# lm2576-adj_powersupply.net
KiCad netlist of a schematic drawn in EAGLE
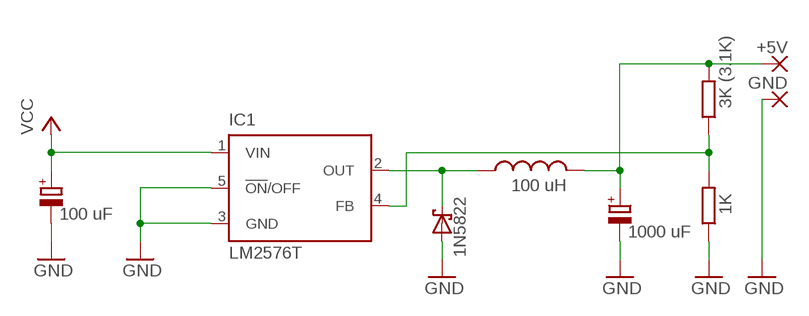
[diagram p0: schematic, sheet 1]

(export (version "E")
  (design (tool "Eeschema 10.0.6"))
  (components
    (comp (ref "+5V")
      (value "2,15/1,0")
      (footprint "eagle-import:2,15_1,0")
      (libsource (lib "eagle-import") (part "2,15/1,0"))
    )
    (comp (ref "C1")
      (value "100 uF")
      (footprint "eagle-import:E7,5-16")
      (libsource (lib "eagle-import") (part "CPOL-EUE7.5-16"))
    )
    (comp (ref "C2")
      (value "1000 uF")
      (footprint "eagle-import:E7,5-16")
      (libsource (lib "eagle-import") (part "CPOL-EUE7.5-16"))
    )
    (comp (ref "D1")
      (value "1N5822")
      (footprint "eagle-import:C4111-15")
      (libsource (lib "eagle-import") (part "1N5908"))
    )
    (comp (ref "GND")
      (value "GND")
      (footprint "eagle-import:2,15_1,0")
      (libsource (lib "eagle-import") (part "2,15/1,0"))
    )
    (comp (ref "IC1")
      (value "LM2576T")
      (footprint "eagle-import:T05D")
      (fields (field (name "MPN") "LM2596T-ADJ/LF02") (field (name "MPN_1") "LM2576T-ADJ"))
      (libsource (lib "eagle-import") (part "LM2596T"))
    )
    (comp (ref "L1")
      (value "100 uH")
      (footprint "eagle-import:6000-XXXX-RC")
      (libsource (lib "eagle-import") (part "L-US6000-XXX-RC"))
    )
    (comp (ref "R1")
      (value "1K")
      (footprint "eagle-import:0207_10")
      (libsource (lib "eagle-import") (part "R-EU_0207/10"))
    )
    (comp (ref "R2")
      (value "3K (3.1K)")
      (footprint "eagle-import:0207_10")
      (libsource (lib "eagle-import") (part "R-EU_0207/10"))
    )
  )
  (nets
    (net (code "1") (name "GND") (class "Default")
      (node (ref "C1") (pin "-") (pinfunction "-_-") (pintype "passive"))
      (node (ref "C2") (pin "-") (pinfunction "-_-") (pintype "passive"))
      (node (ref "D1") (pin "A") (pinfunction "A_A") (pintype "passive"))
      (node (ref "GND") (pin "1") (pinfunction "P_1") (pintype "passive"))
      (node (ref "IC1") (pin "3") (pinfunction "GND_3") (pintype "power_in"))
      (node (ref "IC1") (pin "5") (pinfunction "~{ON}/OFF_5") (pintype "input"))
      (node (ref "R1") (pin "1") (pinfunction "1_1") (pintype "passive"))
    )
    (net (code "2") (name "Net-(+5V-P)") (class "Default")
      (node (ref "+5V") (pin "1") (pinfunction "P_1") (pintype "passive"))
      (node (ref "C2") (pin "+") (pinfunction "+_+") (pintype "passive"))
      (node (ref "L1") (pin "2") (pinfunction "2_2") (pintype "passive"))
      (node (ref "R2") (pin "2") (pinfunction "2_2") (pintype "passive"))
    )
    (net (code "3") (name "Net-(IC1-FB)") (class "Default")
      (node (ref "IC1") (pin "4") (pinfunction "FB_4") (pintype "input"))
      (node (ref "R1") (pin "2") (pinfunction "2_2") (pintype "passive"))
      (node (ref "R2") (pin "1") (pinfunction "1_1") (pintype "passive"))
    )
    (net (code "4") (name "Net-(IC1-OUT)") (class "Default")
      (node (ref "D1") (pin "C") (pinfunction "C_C") (pintype "passive"))
      (node (ref "IC1") (pin "2") (pinfunction "OUT_2") (pintype "output"))
      (node (ref "L1") (pin "1") (pinfunction "1_1") (pintype "passive"))
    )
    (net (code "5") (name "VCC") (class "Default")
      (node (ref "C1") (pin "+") (pinfunction "+_+") (pintype "passive"))
      (node (ref "IC1") (pin "1") (pinfunction "VIN_1") (pintype "input"))
    )
  )
)
